# Analog.net
KiCad netlist of a schematic drawn in Altium Designer
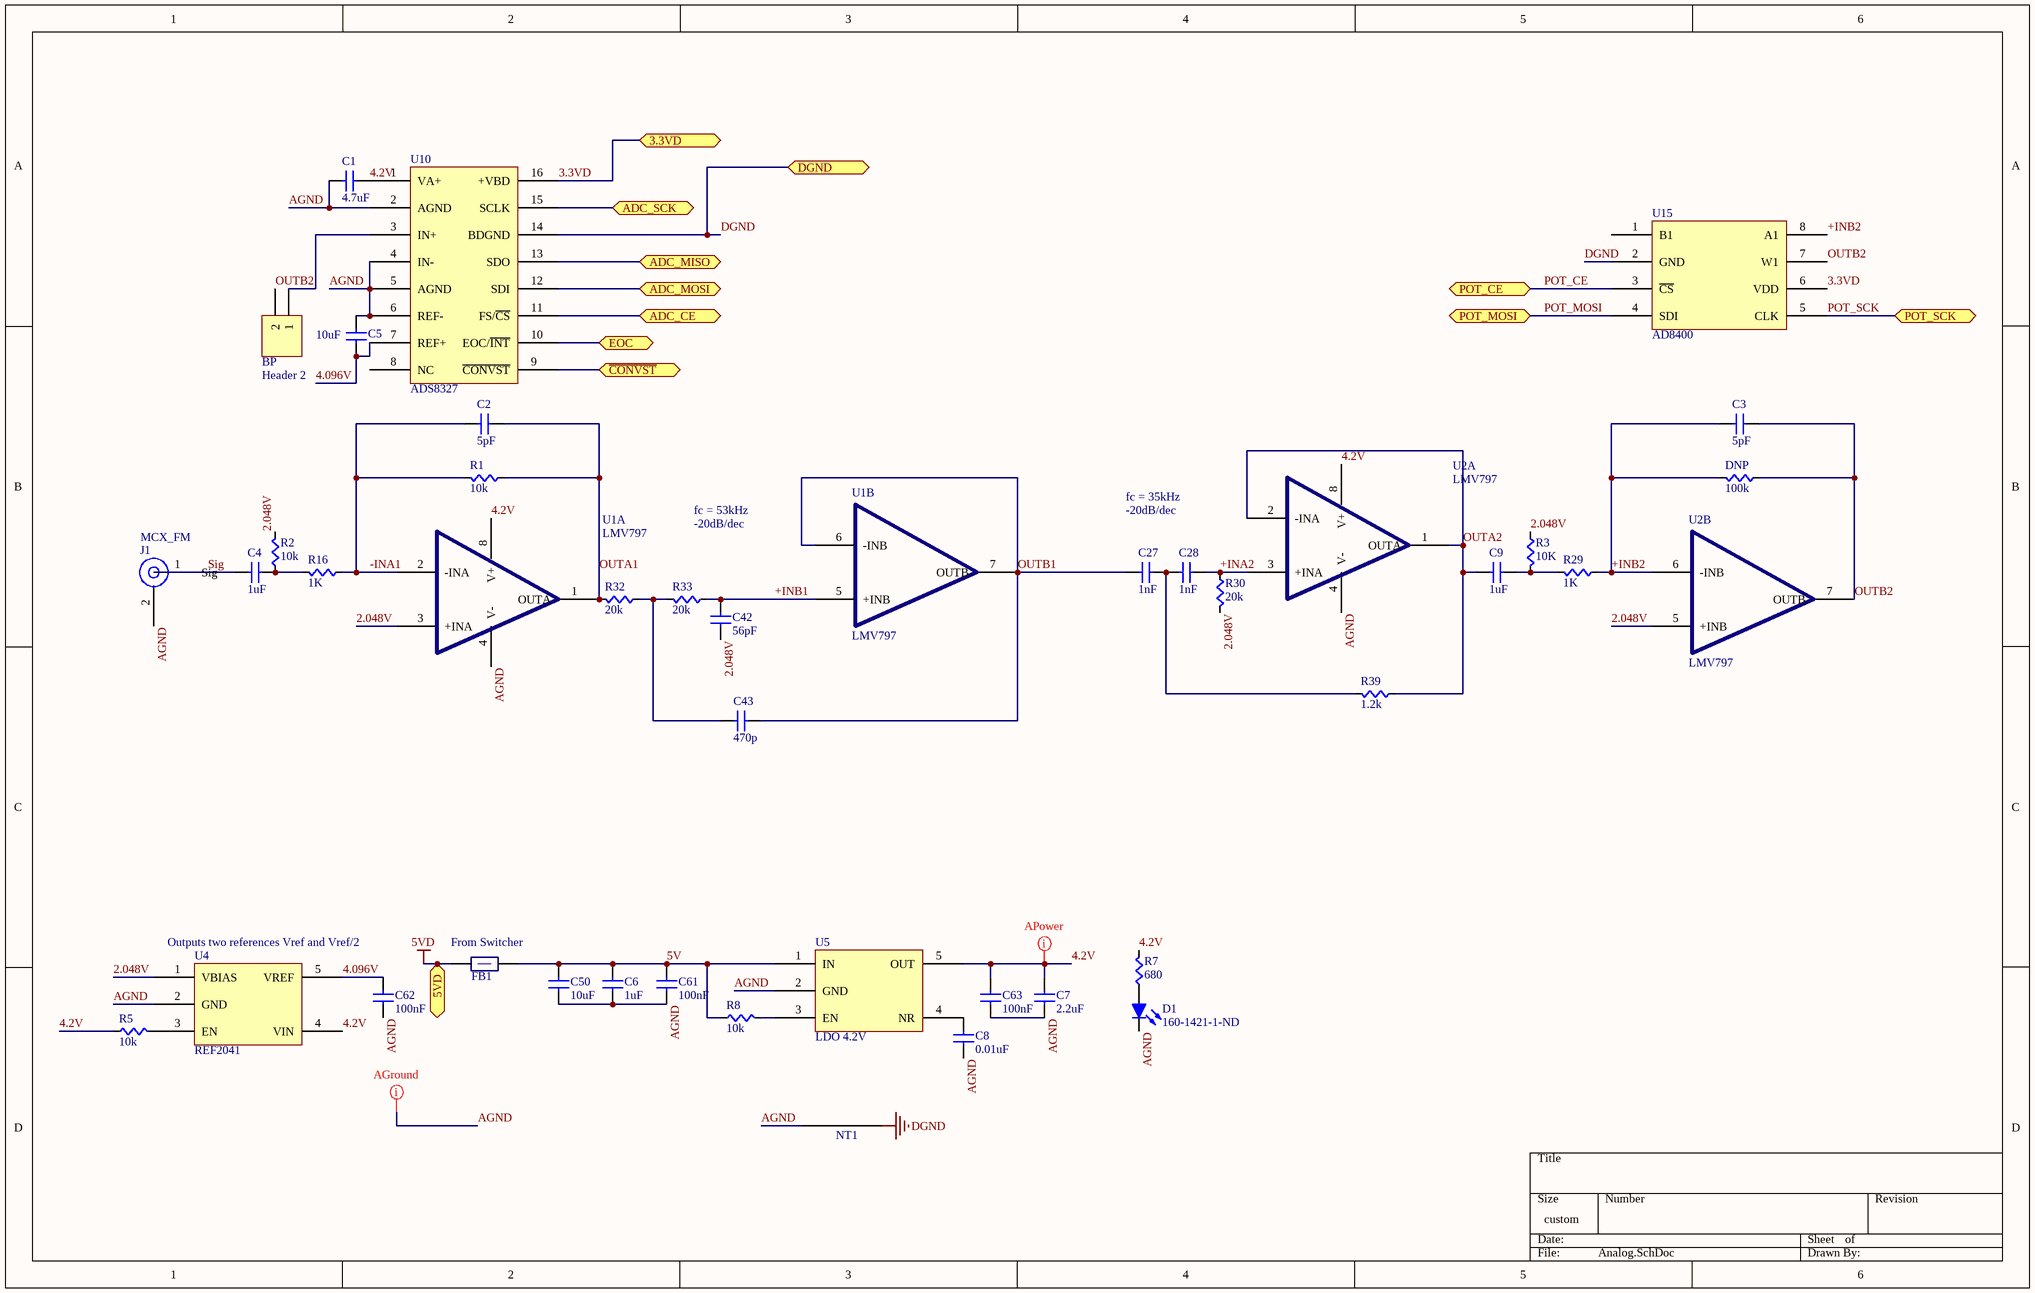
[diagram p0: Analog.SchDoc]

(export (version "E")
  (design (tool "Eeschema 10.0.6"))
  (components
    (comp (ref "BP")
      (value "Header 2")
      (footprint "HDR1X2")
      (description "Header, 2-Pin")
      (fields (field (name "PUBLISHER") "Altium Limited"))
      (libsource (lib "Miscellaneous Connectors") (part "Header 2"))
    )
    (comp (ref "C1")
      (value "4.7uF")
      (footprint "CAPC0603")
      (fields (field (name "Comment") "Cap"))
      (libsource (lib "SubjuGator8") (part "Cap"))
    )
    (comp (ref "C2")
      (value "5pF")
      (footprint "CAPC0603")
      (fields (field (name "Comment") "Cap"))
      (libsource (lib "SubjuGator8") (part "Cap"))
    )
    (comp (ref "C3")
      (value "5pF")
      (footprint "CAPC0603")
      (fields (field (name "Comment") "Cap"))
      (libsource (lib "SubjuGator8") (part "Cap"))
    )
    (comp (ref "C4")
      (value "1uF")
      (footprint "CAPC0603")
      (fields (field (name "Comment") "Cap"))
      (libsource (lib "SubjuGator8") (part "Cap"))
    )
    (comp (ref "C5")
      (value "10uF")
      (footprint "CAPC0603")
      (fields (field (name "Comment") "Cap"))
      (libsource (lib "SubjuGator8") (part "Cap"))
    )
    (comp (ref "C6")
      (value "1uF")
      (footprint "CAPC0603")
      (fields (field (name "Comment") "Cap"))
      (libsource (lib "SubjuGator8") (part "Cap"))
    )
    (comp (ref "C7")
      (value "2.2uF")
      (footprint "CAPC0603")
      (fields (field (name "Comment") "Cap"))
      (libsource (lib "SubjuGator8") (part "Cap"))
    )
    (comp (ref "C8")
      (value "0.01uF")
      (footprint "CAPC0603")
      (fields (field (name "Comment") "Cap"))
      (libsource (lib "SubjuGator8") (part "Cap"))
    )
    (comp (ref "C9")
      (value "1uF")
      (footprint "CAPC0603")
      (fields (field (name "Comment") "Cap"))
      (libsource (lib "SubjuGator8") (part "Cap"))
    )
    (comp (ref "C27")
      (value "1nF")
      (footprint "CAPC0603")
      (fields (field (name "Comment") "Cap"))
      (libsource (lib "SubjuGator8") (part "Cap"))
    )
    (comp (ref "C28")
      (value "1nF")
      (footprint "CAPC0603")
      (fields (field (name "Comment") "Cap"))
      (libsource (lib "SubjuGator8") (part "Cap"))
    )
    (comp (ref "C42")
      (value "56pF")
      (footprint "CAPC0603")
      (fields (field (name "Comment") "Cap"))
      (libsource (lib "SubjuGator8") (part "Cap"))
    )
    (comp (ref "C43")
      (value "470p")
      (footprint "CAPC0603")
      (fields (field (name "Comment") "Cap"))
      (libsource (lib "SubjuGator8") (part "Cap"))
    )
    (comp (ref "C50")
      (value "10uF")
      (footprint "CAPC0603")
      (fields (field (name "Comment") "Cap"))
      (libsource (lib "Passives") (part "Cap"))
    )
    (comp (ref "C61")
      (value "100nF")
      (footprint "CAPC0603")
      (fields (field (name "Comment") "Cap"))
      (libsource (lib "Passives") (part "Cap"))
    )
    (comp (ref "C62")
      (value "100nF")
      (footprint "CAPC0603")
      (fields (field (name "Comment") "Cap"))
      (libsource (lib "Passives") (part "Cap"))
    )
    (comp (ref "C63")
      (value "100nF")
      (footprint "CAPC0603")
      (fields (field (name "Comment") "Cap"))
      (libsource (lib "Passives") (part "Cap"))
    )
    (comp (ref "D1")
      (value "LED-RED")
      (footprint "Hydrophone:LED0805-RED")
      (description "Light Emitting Diode - RED")
      (fields
        (field (name "MANUFACTURER PART NUMBER") "LTST-C171CKT")
        (field (name "MANUFACTURER") "Lite-On Inc")
        (field (name "SUPPLIER PART NUMBER 1") "160-1421-1-ND")
      )
      (libsource (lib "Hydrophone") (part "LED-RED"))
    )
    (comp (ref "DNP")
      (value "100k")
      (footprint "RES0603")
      (fields (field (name "Comment") "Res"))
      (libsource (lib "SubjuGator8") (part "Res"))
    )
    (comp (ref "FB1")
      (value "FBead")
      (footprint "RES0603")
      (description "Ferrite Bead")
      (libsource (lib "Passives") (part "FBead"))
    )
    (comp (ref "J1")
      (value "MCX_FM")
      (footprint "MCX_FEMALE")
      (description "MCX female receptacle RA")
      (libsource (lib "Hydrophone") (part "MCX_FEMALE"))
    )
    (comp (ref "NT1")
      (value "NetTie")
      (footprint "NT_5mil")
      (description "Ties two nets together")
      (libsource (lib "SubjuGator8") (part "NetTie"))
    )
    (comp (ref "R1")
      (value "10k")
      (footprint "RES0603")
      (fields (field (name "Comment") "Res"))
      (libsource (lib "SubjuGator8") (part "Res"))
    )
    (comp (ref "R2")
      (value "10k")
      (footprint "RES0603")
      (fields (field (name "Comment") "Res"))
      (libsource (lib "SubjuGator8") (part "Res"))
    )
    (comp (ref "R3")
      (value "10K")
      (footprint "RES0603")
      (fields (field (name "Comment") "Res"))
      (libsource (lib "SubjuGator8") (part "Res"))
    )
    (comp (ref "R5")
      (value "10k")
      (footprint "RES0603")
      (fields (field (name "Comment") "Res"))
      (libsource (lib "SubjuGator8") (part "Res"))
    )
    (comp (ref "R7")
      (value "680")
      (footprint "RES0603")
      (fields (field (name "Comment") "Res"))
      (libsource (lib "SubjuGator8") (part "Res"))
    )
    (comp (ref "R8")
      (value "10k")
      (footprint "RES0603")
      (fields (field (name "Comment") "Res"))
      (libsource (lib "SubjuGator8") (part "Res"))
    )
    (comp (ref "R16")
      (value "1K")
      (footprint "RES0603")
      (fields (field (name "Comment") "Res"))
      (libsource (lib "SubjuGator8") (part "Res"))
    )
    (comp (ref "R29")
      (value "1K")
      (footprint "RES0603")
      (fields (field (name "Comment") "Res"))
      (libsource (lib "SubjuGator8") (part "Res"))
    )
    (comp (ref "R30")
      (value "20k")
      (footprint "RES0603")
      (fields (field (name "Comment") "Res"))
      (libsource (lib "SubjuGator8") (part "Res"))
    )
    (comp (ref "R32")
      (value "20k")
      (footprint "RES0603")
      (fields (field (name "Comment") "Res"))
      (libsource (lib "SubjuGator8") (part "Res"))
    )
    (comp (ref "R33")
      (value "20k")
      (footprint "RES0603")
      (fields (field (name "Comment") "Res"))
      (libsource (lib "SubjuGator8") (part "Res"))
    )
    (comp (ref "R39")
      (value "1.2k")
      (footprint "RES0603")
      (fields (field (name "Comment") "Res"))
      (libsource (lib "SubjuGator8") (part "Res"))
    )
    (comp (ref "U1")
      (value "LMV797")
      (footprint "TSSOP-8N")
      (description "IC OPAMP GP 17MHZ RRO 8VSSOP")
      (libsource (lib "ICs") (part "LMV797"))
    )
    (comp (ref "U2")
      (value "LMV797")
      (footprint "TSSOP-8N")
      (description "IC OPAMP GP 17MHZ RRO 8VSSOP")
      (libsource (lib "ICs") (part "LMV797"))
    )
    (comp (ref "U4")
      (value "REF2041")
      (footprint "SOT23-5")
      (description "IC VREF SERIES 2.05V/4.096V 5SOT")
      (libsource (lib "SubjuGator8") (part "REF2041"))
    )
    (comp (ref "U5")
      (value "LDO 4.2V")
      (footprint "sot23-5")
      (description "IC REG LDO 4.2V 0.2A 5SOT")
      (libsource (lib "SubjuGator8") (part "LDO 4.2V 200mA"))
    )
    (comp (ref "U10")
      (value "ADS8327")
      (footprint "TSSOP-16pin")
      (description "IC ADC 16BIT 500KSPS 16-TSSOP")
      (libsource (lib "SubjuGator8") (part "ADC 16bit 500k"))
    )
    (comp (ref "U15")
      (value "AD8400")
      (footprint "SOIC-8PIN")
      (description "IC DGTL POT 8BIT 100K 1CH 8-SOIC")
      (libsource (lib "ICs") (part "AD8400"))
    )
  )
  (nets
    (net (code "1") (name "/+INA2") (class "Default")
      (node (ref "C28") (pin "2") (pinfunction "B_2") (pintype "passive"))
      (node (ref "R30") (pin "2") (pinfunction "B_2") (pintype "passive"))
      (node (ref "U2") (pin "3") (pinfunction "+INA_3") (pintype "passive"))
    )
    (net (code "2") (name "/+INB1") (class "Default")
      (node (ref "C42") (pin "2") (pinfunction "B_2") (pintype "passive"))
      (node (ref "R33") (pin "2") (pinfunction "B_2") (pintype "passive"))
      (node (ref "U1") (pin "5") (pinfunction "+INB_5") (pintype "passive"))
    )
    (net (code "3") (name "/+INB2") (class "Default")
      (node (ref "C3") (pin "1") (pinfunction "A_1") (pintype "passive"))
      (node (ref "DNP") (pin "1") (pinfunction "A_1") (pintype "passive"))
      (node (ref "R29") (pin "2") (pinfunction "B_2") (pintype "passive"))
      (node (ref "U15") (pin "8") (pinfunction "A1_8") (pintype "passive"))
      (node (ref "U2") (pin "6") (pinfunction "-INB_6") (pintype "passive"))
    )
    (net (code "4") (name "/-INA1") (class "Default")
      (node (ref "C2") (pin "1") (pinfunction "A_1") (pintype "passive"))
      (node (ref "R1") (pin "1") (pinfunction "A_1") (pintype "passive"))
      (node (ref "R16") (pin "2") (pinfunction "B_2") (pintype "passive"))
      (node (ref "U1") (pin "2") (pinfunction "-INA_2") (pintype "passive"))
    )
    (net (code "5") (name "/2.048V") (class "Default")
      (node (ref "C42") (pin "1") (pinfunction "A_1") (pintype "passive"))
      (node (ref "R2") (pin "1") (pinfunction "A_1") (pintype "passive"))
      (node (ref "R3") (pin "2") (pinfunction "B_2") (pintype "passive"))
      (node (ref "R30") (pin "1") (pinfunction "A_1") (pintype "passive"))
      (node (ref "U1") (pin "3") (pinfunction "+INA_3") (pintype "passive"))
      (node (ref "U2") (pin "5") (pinfunction "+INB_5") (pintype "passive"))
      (node (ref "U4") (pin "1") (pinfunction "VBIAS_1") (pintype "passive"))
    )
    (net (code "6") (name "/3.3VD") (class "Default")
      (node (ref "U10") (pin "16") (pinfunction "+VBD_16") (pintype "passive"))
      (node (ref "U15") (pin "6") (pinfunction "VDD_6") (pintype "passive"))
    )
    (net (code "7") (name "/4.2V") (class "Default")
      (node (ref "C1") (pin "2") (pinfunction "B_2") (pintype "passive"))
      (node (ref "C63") (pin "1") (pinfunction "A_1") (pintype "passive"))
      (node (ref "C7") (pin "2") (pinfunction "B_2") (pintype "passive"))
      (node (ref "R5") (pin "2") (pinfunction "B_2") (pintype "passive"))
      (node (ref "R7") (pin "1") (pinfunction "A_1") (pintype "passive"))
      (node (ref "U1") (pin "8") (pinfunction "V+_8") (pintype "passive"))
      (node (ref "U10") (pin "1") (pinfunction "VA+_1") (pintype "passive"))
      (node (ref "U2") (pin "8") (pinfunction "V+_8") (pintype "passive"))
      (node (ref "U4") (pin "4") (pinfunction "VIN_4") (pintype "passive"))
      (node (ref "U5") (pin "5") (pinfunction "OUT_5") (pintype "passive"))
    )
    (net (code "8") (name "/4.096V") (class "Default")
      (node (ref "C5") (pin "2") (pinfunction "B_2") (pintype "passive"))
      (node (ref "C62") (pin "1") (pinfunction "A_1") (pintype "passive"))
      (node (ref "U10") (pin "7") (pinfunction "REF+_7") (pintype "passive"))
      (node (ref "U4") (pin "5") (pinfunction "VREF_5") (pintype "passive"))
    )
    (net (code "9") (name "/5V") (class "Default")
      (node (ref "C50") (pin "1") (pinfunction "A_1") (pintype "passive"))
      (node (ref "C6") (pin "2") (pinfunction "B_2") (pintype "passive"))
      (node (ref "C61") (pin "1") (pinfunction "A_1") (pintype "passive"))
      (node (ref "FB1") (pin "2") (pinfunction "B_2") (pintype "passive"))
      (node (ref "R8") (pin "2") (pinfunction "B_2") (pintype "passive"))
      (node (ref "U5") (pin "1") (pinfunction "IN_1") (pintype "passive"))
    )
    (net (code "10") (name "/ADC_CE") (class "Default")
      (node (ref "U10") (pin "11") (pinfunction "FS/~{CS}_11") (pintype "passive"))
    )
    (net (code "11") (name "/ADC_MISO") (class "Default")
      (node (ref "U10") (pin "13") (pinfunction "SDO_13") (pintype "passive"))
    )
    (net (code "12") (name "/ADC_MOSI") (class "Default")
      (node (ref "U10") (pin "12") (pinfunction "SDI_12") (pintype "passive"))
    )
    (net (code "13") (name "/ADC_SCK") (class "Default")
      (node (ref "U10") (pin "15") (pinfunction "SCLK_15") (pintype "passive"))
    )
    (net (code "14") (name "/AGND") (class "Default")
      (node (ref "C1") (pin "1") (pinfunction "A_1") (pintype "passive"))
      (node (ref "C5") (pin "1") (pinfunction "A_1") (pintype "passive"))
      (node (ref "C50") (pin "2") (pinfunction "B_2") (pintype "passive"))
      (node (ref "C6") (pin "1") (pinfunction "A_1") (pintype "passive"))
      (node (ref "C61") (pin "2") (pinfunction "B_2") (pintype "passive"))
      (node (ref "C62") (pin "2") (pinfunction "B_2") (pintype "passive"))
      (node (ref "C63") (pin "2") (pinfunction "B_2") (pintype "passive"))
      (node (ref "C7") (pin "1") (pinfunction "A_1") (pintype "passive"))
      (node (ref "C8") (pin "1") (pinfunction "A_1") (pintype "passive"))
      (node (ref "D1") (pin "1") (pinfunction "K_1") (pintype "passive"))
      (node (ref "J1") (pin "2") (pinfunction "GND_2") (pintype "passive"))
      (node (ref "NT1") (pin "1") (pinfunction "1_1") (pintype "passive"))
      (node (ref "U1") (pin "4") (pinfunction "V-_4") (pintype "passive"))
      (node (ref "U10") (pin "2") (pinfunction "AGND_2") (pintype "passive"))
      (node (ref "U10") (pin "4") (pinfunction "IN-_4") (pintype "passive"))
      (node (ref "U10") (pin "5") (pinfunction "AGND_5") (pintype "passive"))
      (node (ref "U10") (pin "6") (pinfunction "REF-_6") (pintype "passive"))
      (node (ref "U2") (pin "4") (pinfunction "V-_4") (pintype "passive"))
      (node (ref "U4") (pin "2") (pinfunction "GND_2") (pintype "passive"))
      (node (ref "U5") (pin "2") (pinfunction "GND_2") (pintype "passive"))
    )
    (net (code "15") (name "/EOC") (class "Default")
      (node (ref "U10") (pin "10") (pinfunction "EOC/~{INT}_10") (pintype "passive"))
    )
    (net (code "16") (name "/OUTA1") (class "Default")
      (node (ref "C2") (pin "2") (pinfunction "B_2") (pintype "passive"))
      (node (ref "R1") (pin "2") (pinfunction "B_2") (pintype "passive"))
      (node (ref "R32") (pin "1") (pinfunction "A_1") (pintype "passive"))
      (node (ref "U1") (pin "1") (pinfunction "OUTA_1") (pintype "passive"))
    )
    (net (code "17") (name "/OUTA2") (class "Default")
      (node (ref "C9") (pin "1") (pinfunction "A_1") (pintype "passive"))
      (node (ref "R39") (pin "2") (pinfunction "B_2") (pintype "passive"))
      (node (ref "U2") (pin "1") (pinfunction "OUTA_1") (pintype "passive"))
      (node (ref "U2") (pin "2") (pinfunction "-INA_2") (pintype "passive"))
    )
    (net (code "18") (name "/OUTB1") (class "Default")
      (node (ref "C27") (pin "1") (pinfunction "A_1") (pintype "passive"))
      (node (ref "C43") (pin "1") (pinfunction "A_1") (pintype "passive"))
      (node (ref "U1") (pin "6") (pinfunction "-INB_6") (pintype "passive"))
      (node (ref "U1") (pin "7") (pinfunction "OUTB_7") (pintype "passive"))
    )
    (net (code "19") (name "/OUTB2") (class "Default")
      (node (ref "BP") (pin "2") (pinfunction "2_2") (pintype "passive"))
      (node (ref "C3") (pin "2") (pinfunction "B_2") (pintype "passive"))
      (node (ref "DNP") (pin "2") (pinfunction "B_2") (pintype "passive"))
      (node (ref "U15") (pin "7") (pinfunction "W1_7") (pintype "passive"))
      (node (ref "U2") (pin "7") (pinfunction "OUTB_7") (pintype "passive"))
    )
    (net (code "20") (name "/POT_CE") (class "Default")
      (node (ref "U15") (pin "3") (pinfunction "~{CS}_3") (pintype "passive"))
    )
    (net (code "21") (name "/POT_MOSI") (class "Default")
      (node (ref "U15") (pin "4") (pinfunction "SDI_4") (pintype "passive"))
    )
    (net (code "22") (name "/POT_SCK") (class "Default")
      (node (ref "U15") (pin "5") (pinfunction "CLK_5") (pintype "passive"))
    )
    (net (code "23") (name "/Sig") (class "Default")
      (node (ref "C4") (pin "1") (pinfunction "A_1") (pintype "passive"))
      (node (ref "J1") (pin "1") (pinfunction "Sig_1") (pintype "passive"))
    )
    (net (code "24") (name "/~{CONVST}") (class "Default")
      (node (ref "U10") (pin "9") (pinfunction "~{CONVST}_9") (pintype "passive"))
    )
    (net (code "25") (name "5VD") (class "Default")
      (node (ref "FB1") (pin "1") (pinfunction "A_1") (pintype "passive"))
    )
    (net (code "26") (name "DGND") (class "Default")
      (node (ref "NT1") (pin "2") (pinfunction "2_2") (pintype "passive"))
      (node (ref "U10") (pin "14") (pinfunction "BDGND_14") (pintype "passive"))
      (node (ref "U15") (pin "2") (pinfunction "GND_2") (pintype "passive"))
    )
    (net (code "27") (name "Net-(C4-B)") (class "Default")
      (node (ref "C4") (pin "2") (pinfunction "B_2") (pintype "passive"))
      (node (ref "R16") (pin "1") (pinfunction "A_1") (pintype "passive"))
      (node (ref "R2") (pin "2") (pinfunction "B_2") (pintype "passive"))
    )
    (net (code "28") (name "Net-(C8-B)") (class "Default")
      (node (ref "C8") (pin "2") (pinfunction "B_2") (pintype "passive"))
      (node (ref "U5") (pin "4") (pinfunction "NR_4") (pintype "passive"))
    )
    (net (code "29") (name "Net-(C9-B)") (class "Default")
      (node (ref "C9") (pin "2") (pinfunction "B_2") (pintype "passive"))
      (node (ref "R29") (pin "1") (pinfunction "A_1") (pintype "passive"))
      (node (ref "R3") (pin "1") (pinfunction "A_1") (pintype "passive"))
    )
    (net (code "30") (name "Net-(C27-B)") (class "Default")
      (node (ref "C27") (pin "2") (pinfunction "B_2") (pintype "passive"))
      (node (ref "C28") (pin "1") (pinfunction "A_1") (pintype "passive"))
      (node (ref "R39") (pin "1") (pinfunction "A_1") (pintype "passive"))
    )
    (net (code "31") (name "Net-(C43-B)") (class "Default")
      (node (ref "C43") (pin "2") (pinfunction "B_2") (pintype "passive"))
      (node (ref "R32") (pin "2") (pinfunction "B_2") (pintype "passive"))
      (node (ref "R33") (pin "1") (pinfunction "A_1") (pintype "passive"))
    )
    (net (code "32") (name "Net-(D1-A)") (class "Default")
      (node (ref "D1") (pin "2") (pinfunction "A_2") (pintype "passive"))
      (node (ref "R7") (pin "2") (pinfunction "B_2") (pintype "passive"))
    )
    (net (code "33") (name "Net-(R5-A)") (class "Default")
      (node (ref "R5") (pin "1") (pinfunction "A_1") (pintype "passive"))
      (node (ref "U4") (pin "3") (pinfunction "EN_3") (pintype "passive"))
    )
    (net (code "34") (name "Net-(R8-A)") (class "Default")
      (node (ref "R8") (pin "1") (pinfunction "A_1") (pintype "passive"))
      (node (ref "U5") (pin "3") (pinfunction "EN_3") (pintype "passive"))
    )
    (net (code "35") (name "Net-(U10-IN+)") (class "Default")
      (node (ref "BP") (pin "1") (pinfunction "1_1") (pintype "passive"))
      (node (ref "U10") (pin "3") (pinfunction "IN+_3") (pintype "passive"))
    )
    (net (code "36") (name "unconnected-(U10-NC-Pad8)") (class "Default")
      (node (ref "U10") (pin "8") (pinfunction "NC_8") (pintype "passive"))
    )
    (net (code "37") (name "unconnected-(U15-B1-Pad1)") (class "Default")
      (node (ref "U15") (pin "1") (pinfunction "B1_1") (pintype "passive"))
    )
  )
)
